# Chocolate_Vending_Machine_V2_2.net
KiCad netlist of a schematic drawn in Altium Designer
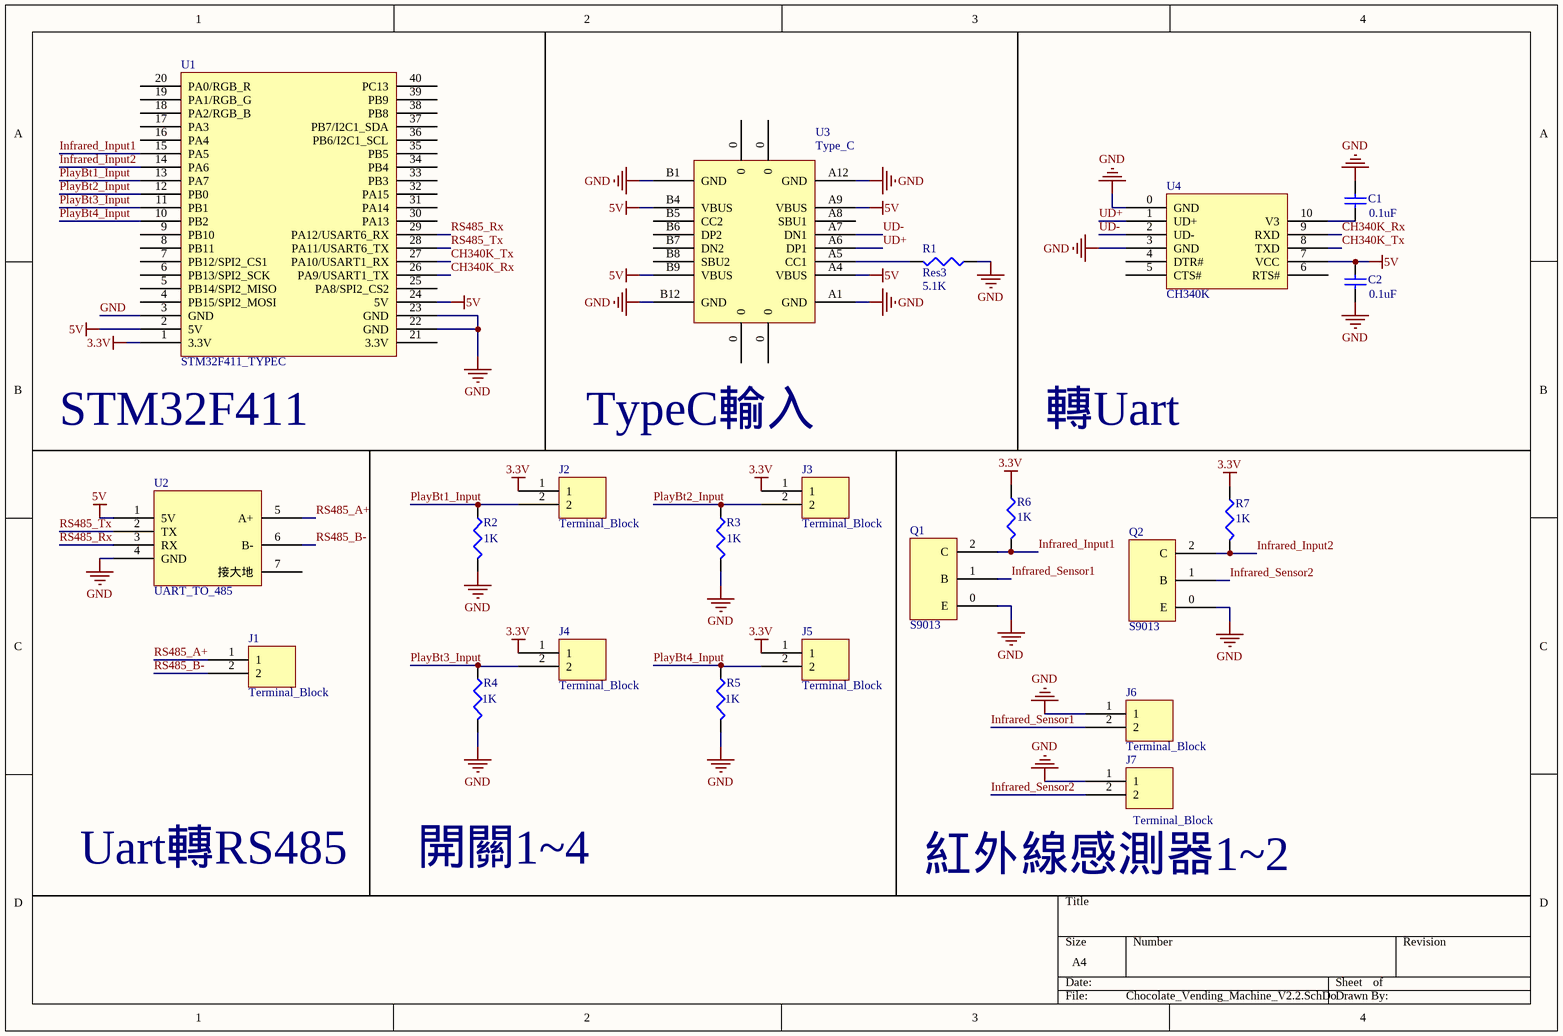
[diagram p0: Chocolate_Vending_Machine_V2.2.SchDoc]

(export (version "E")
  (design (tool "Eeschema 10.0.6"))
  (components
    (comp (ref "C1")
      (value "0.1uF")
      (footprint "1608[0603]")
      (description "Capacitor (Semiconductor SIM Model)")
      (fields (field (name "Comment") "Cap Semi") (field (name "PUBLISHER") "Altium Limited"))
      (libsource (lib "Miscellaneous Devices") (part "Cap Semi"))
    )
    (comp (ref "C2")
      (value "0.1uF")
      (footprint "1608[0603]")
      (description "Capacitor (Semiconductor SIM Model)")
      (fields (field (name "Comment") "Cap Semi") (field (name "PUBLISHER") "Altium Limited"))
      (libsource (lib "Miscellaneous Devices") (part "Cap Semi"))
    )
    (comp (ref "J1")
      (value "Terminal_Block")
      (footprint "terminal block")
      (libsource (lib "Lab_share") (part "Terminal Block"))
    )
    (comp (ref "J2")
      (value "Terminal_Block")
      (footprint "terminal block")
      (libsource (lib "Lab_share") (part "Terminal Block"))
    )
    (comp (ref "J3")
      (value "Terminal_Block")
      (footprint "terminal block")
      (libsource (lib "Lab_share") (part "Terminal Block"))
    )
    (comp (ref "J4")
      (value "Terminal_Block")
      (footprint "terminal block")
      (libsource (lib "Lab_share") (part "Terminal Block"))
    )
    (comp (ref "J5")
      (value "Terminal_Block")
      (footprint "terminal block")
      (libsource (lib "Lab_share") (part "Terminal Block"))
    )
    (comp (ref "J6")
      (value "Terminal_Block")
      (footprint "terminal block")
      (libsource (lib "Lab_share") (part "Terminal Block"))
    )
    (comp (ref "J7")
      (value "Terminal_Block")
      (footprint "terminal block")
      (libsource (lib "Lab_share") (part "Terminal Block"))
    )
    (comp (ref "Q1") (value "S9013") (footprint "S9013") (libsource (lib "Lab_share") (part "S9013")))
    (comp (ref "Q2") (value "S9013") (footprint "S9013") (libsource (lib "Lab_share") (part "S9013")))
    (comp (ref "R1")
      (value "Res3")
      (footprint "J1-0603")
      (description "Resistor")
      (fields (field (name "ALTIUM_VALUE") "5.1K") (field (name "PUBLISHER") "Altium Limited"))
      (libsource (lib "Miscellaneous Devices") (part "Res3"))
    )
    (comp (ref "R2")
      (value "1K")
      (footprint "J1-0603")
      (description "Resistor")
      (fields (field (name "Comment") "Res3") (field (name "PUBLISHER") "Altium Limited"))
      (libsource (lib "Miscellaneous Devices") (part "Res3"))
    )
    (comp (ref "R3")
      (value "1K")
      (footprint "J1-0603")
      (description "Resistor")
      (fields (field (name "Comment") "Res3") (field (name "PUBLISHER") "Altium Limited"))
      (libsource (lib "Miscellaneous Devices") (part "Res3"))
    )
    (comp (ref "R4")
      (value "1K")
      (footprint "J1-0603")
      (description "Resistor")
      (fields (field (name "Comment") "Res3") (field (name "PUBLISHER") "Altium Limited"))
      (libsource (lib "Miscellaneous Devices") (part "Res3"))
    )
    (comp (ref "R5")
      (value "1K")
      (footprint "J1-0603")
      (description "Resistor")
      (fields (field (name "Comment") "Res3") (field (name "PUBLISHER") "Altium Limited"))
      (libsource (lib "Miscellaneous Devices") (part "Res3"))
    )
    (comp (ref "R6")
      (value "1K")
      (footprint "J1-0603")
      (description "Resistor")
      (fields (field (name "Comment") "Res3") (field (name "PUBLISHER") "Altium Limited"))
      (libsource (lib "Miscellaneous Devices") (part "Res3"))
    )
    (comp (ref "R7")
      (value "1K")
      (footprint "J1-0603")
      (description "Resistor")
      (fields (field (name "Comment") "Res3") (field (name "PUBLISHER") "Altium Limited"))
      (libsource (lib "Miscellaneous Devices") (part "Res3"))
    )
    (comp (ref "U1")
      (value "STM32F411_TYPEC")
      (footprint "STM32F411_TypeC")
      (libsource (lib "Lab_share") (part "STM32F411_TYPEC"))
    )
    (comp (ref "U2")
      (value "UART_TO_485")
      (footprint "UART_TO_RS485")
      (libsource (lib "Lab_share") (part "UART_TO_485"))
    )
    (comp (ref "U3") (value "Type_C") (footprint "Type_C_V2") (libsource (lib "Lab_share") (part "Type_C")))
    (comp (ref "U4") (value "CH340K") (footprint "CH340K_V1") (libsource (lib "Lab_share") (part "CH340K")))
  )
  (nets
    (net (code "1") (name "/CH340K_Rx") (class "Default")
      (node (ref "U1") (pin "26") (pinfunction "PA9/USART1_TX_26") (pintype "passive"))
      (node (ref "U4") (pin "9") (pinfunction "RXD_9") (pintype "passive"))
    )
    (net (code "2") (name "/CH340K_Tx") (class "Default")
      (node (ref "U1") (pin "27") (pinfunction "PA10/USART1_RX_27") (pintype "passive"))
      (node (ref "U4") (pin "8") (pinfunction "TXD_8") (pintype "passive"))
    )
    (net (code "3") (name "/Infrared_Input1") (class "Default")
      (node (ref "Q1") (pin "2") (pinfunction "C_2") (pintype "passive"))
      (node (ref "R6") (pin "2") (pinfunction "2_2") (pintype "passive"))
      (node (ref "U1") (pin "15") (pinfunction "PA5_15") (pintype "passive"))
    )
    (net (code "4") (name "/Infrared_Input2") (class "Default")
      (node (ref "Q2") (pin "2") (pinfunction "C_2") (pintype "passive"))
      (node (ref "R7") (pin "2") (pinfunction "2_2") (pintype "passive"))
      (node (ref "U1") (pin "14") (pinfunction "PA6_14") (pintype "passive"))
    )
    (net (code "5") (name "/Infrared_Sensor1") (class "Default")
      (node (ref "J6") (pin "2") (pinfunction "2_2") (pintype "passive"))
      (node (ref "Q1") (pin "1") (pinfunction "B_1") (pintype "passive"))
    )
    (net (code "6") (name "/Infrared_Sensor2") (class "Default")
      (node (ref "J7") (pin "2") (pinfunction "2_2") (pintype "passive"))
      (node (ref "Q2") (pin "1") (pinfunction "B_1") (pintype "passive"))
    )
    (net (code "7") (name "/PlayBt1_Input") (class "Default")
      (node (ref "J2") (pin "2") (pinfunction "2_2") (pintype "passive"))
      (node (ref "R2") (pin "1") (pinfunction "1_1") (pintype "passive"))
      (node (ref "U1") (pin "13") (pinfunction "PA7_13") (pintype "passive"))
    )
    (net (code "8") (name "/PlayBt2_Input") (class "Default")
      (node (ref "J3") (pin "2") (pinfunction "2_2") (pintype "passive"))
      (node (ref "R3") (pin "1") (pinfunction "1_1") (pintype "passive"))
      (node (ref "U1") (pin "12") (pinfunction "PB0_12") (pintype "passive"))
    )
    (net (code "9") (name "/PlayBt3_Input") (class "Default")
      (node (ref "J4") (pin "2") (pinfunction "2_2") (pintype "passive"))
      (node (ref "R4") (pin "1") (pinfunction "1_1") (pintype "passive"))
      (node (ref "U1") (pin "11") (pinfunction "PB1_11") (pintype "passive"))
    )
    (net (code "10") (name "/PlayBt4_Input") (class "Default")
      (node (ref "J5") (pin "2") (pinfunction "2_2") (pintype "passive"))
      (node (ref "R5") (pin "1") (pinfunction "1_1") (pintype "passive"))
      (node (ref "U1") (pin "10") (pinfunction "PB2_10") (pintype "passive"))
    )
    (net (code "11") (name "/RS485_A+") (class "Default")
      (node (ref "J1") (pin "1") (pinfunction "1_1") (pintype "passive"))
      (node (ref "U2") (pin "5") (pinfunction "A+_5") (pintype "passive"))
    )
    (net (code "12") (name "/RS485_B-") (class "Default")
      (node (ref "J1") (pin "2") (pinfunction "2_2") (pintype "passive"))
      (node (ref "U2") (pin "6") (pinfunction "B-_6") (pintype "passive"))
    )
    (net (code "13") (name "/RS485_Rx") (class "Default")
      (node (ref "U1") (pin "29") (pinfunction "PA12/USART6_RX_29") (pintype "passive"))
      (node (ref "U2") (pin "3") (pinfunction "RX_3") (pintype "passive"))
    )
    (net (code "14") (name "/RS485_Tx") (class "Default")
      (node (ref "U1") (pin "28") (pinfunction "PA11/USART6_TX_28") (pintype "passive"))
      (node (ref "U2") (pin "2") (pinfunction "TX_2") (pintype "passive"))
    )
    (net (code "15") (name "/UD+") (class "Default")
      (node (ref "U3") (pin "A6") (pinfunction "DP1_A6") (pintype "passive"))
      (node (ref "U4") (pin "1") (pinfunction "UD+_1") (pintype "passive"))
    )
    (net (code "16") (name "/UD-") (class "Default")
      (node (ref "U3") (pin "A7") (pinfunction "DN1_A7") (pintype "passive"))
      (node (ref "U4") (pin "2") (pinfunction "UD-_2") (pintype "passive"))
    )
    (net (code "17") (name "3.3V") (class "Default")
      (node (ref "J2") (pin "1") (pinfunction "1_1") (pintype "passive"))
      (node (ref "J3") (pin "1") (pinfunction "1_1") (pintype "passive"))
      (node (ref "J4") (pin "1") (pinfunction "1_1") (pintype "passive"))
      (node (ref "J5") (pin "1") (pinfunction "1_1") (pintype "passive"))
      (node (ref "R6") (pin "1") (pinfunction "1_1") (pintype "passive"))
      (node (ref "R7") (pin "1") (pinfunction "1_1") (pintype "passive"))
      (node (ref "U1") (pin "1") (pinfunction "3.3V_1") (pintype "passive"))
    )
    (net (code "18") (name "5V") (class "Default")
      (node (ref "C2") (pin "2") (pinfunction "2_2") (pintype "passive"))
      (node (ref "U1") (pin "2") (pinfunction "5V_2") (pintype "passive"))
      (node (ref "U1") (pin "24") (pinfunction "5V_24") (pintype "passive"))
      (node (ref "U2") (pin "1") (pinfunction "5V_1") (pintype "passive"))
      (node (ref "U3") (pin "A4") (pinfunction "VBUS_A4") (pintype "passive"))
      (node (ref "U3") (pin "A9") (pinfunction "VBUS_A9") (pintype "passive"))
      (node (ref "U3") (pin "B4") (pinfunction "VBUS_B4") (pintype "passive"))
      (node (ref "U3") (pin "B9") (pinfunction "VBUS_B9") (pintype "passive"))
      (node (ref "U4") (pin "7") (pinfunction "VCC_7") (pintype "passive"))
    )
    (net (code "19") (name "GND") (class "Default")
      (node (ref "C1") (pin "2") (pinfunction "2_2") (pintype "passive"))
      (node (ref "C2") (pin "1") (pinfunction "1_1") (pintype "passive"))
      (node (ref "J6") (pin "1") (pinfunction "1_1") (pintype "passive"))
      (node (ref "J7") (pin "1") (pinfunction "1_1") (pintype "passive"))
      (node (ref "Q1") (pin "0") (pinfunction "E_0") (pintype "passive"))
      (node (ref "Q2") (pin "0") (pinfunction "E_0") (pintype "passive"))
      (node (ref "R1") (pin "1") (pinfunction "1_1") (pintype "passive"))
      (node (ref "R2") (pin "2") (pinfunction "2_2") (pintype "passive"))
      (node (ref "R3") (pin "2") (pinfunction "2_2") (pintype "passive"))
      (node (ref "R4") (pin "2") (pinfunction "2_2") (pintype "passive"))
      (node (ref "R5") (pin "2") (pinfunction "2_2") (pintype "passive"))
      (node (ref "U1") (pin "22") (pinfunction "GND_22") (pintype "passive"))
      (node (ref "U1") (pin "23") (pinfunction "GND_23") (pintype "passive"))
      (node (ref "U1") (pin "3") (pinfunction "GND_3") (pintype "passive"))
      (node (ref "U2") (pin "4") (pinfunction "GND_4") (pintype "passive"))
      (node (ref "U3") (pin "A1") (pinfunction "GND_A1") (pintype "passive"))
      (node (ref "U3") (pin "A12") (pinfunction "GND_A12") (pintype "passive"))
      (node (ref "U3") (pin "B1") (pinfunction "GND_B1") (pintype "passive"))
      (node (ref "U3") (pin "B12") (pinfunction "GND_B12") (pintype "passive"))
      (node (ref "U4") (pin "0") (pinfunction "GND_0") (pintype "passive"))
      (node (ref "U4") (pin "3") (pinfunction "GND_3") (pintype "passive"))
    )
    (net (code "20") (name "Net-(U3-CC1)") (class "Default")
      (node (ref "R1") (pin "2") (pinfunction "2_2") (pintype "passive"))
      (node (ref "U3") (pin "A5") (pinfunction "CC1_A5") (pintype "passive"))
    )
    (net (code "21") (name "Net-(U4-V3)") (class "Default")
      (node (ref "C1") (pin "1") (pinfunction "1_1") (pintype "passive"))
      (node (ref "U4") (pin "10") (pinfunction "V3_10") (pintype "passive"))
    )
    (net (code "22") (name "unconnected-(U1-3.3V-Pad21)") (class "Default")
      (node (ref "U1") (pin "21") (pinfunction "3.3V_21") (pintype "passive"))
    )
    (net (code "23") (name "unconnected-(U1-PA0{slash}RGB_R-Pad20)") (class "Default")
      (node (ref "U1") (pin "20") (pinfunction "PA0/RGB_R_20") (pintype "passive"))
    )
    (net (code "24") (name "unconnected-(U1-PA1{slash}RGB_G-Pad19)") (class "Default")
      (node (ref "U1") (pin "19") (pinfunction "PA1/RGB_G_19") (pintype "passive"))
    )
    (net (code "25") (name "unconnected-(U1-PA2{slash}RGB_B-Pad18)") (class "Default")
      (node (ref "U1") (pin "18") (pinfunction "PA2/RGB_B_18") (pintype "passive"))
    )
    (net (code "26") (name "unconnected-(U1-PA3-Pad17)") (class "Default")
      (node (ref "U1") (pin "17") (pinfunction "PA3_17") (pintype "passive"))
    )
    (net (code "27") (name "unconnected-(U1-PA4-Pad16)") (class "Default")
      (node (ref "U1") (pin "16") (pinfunction "PA4_16") (pintype "passive"))
    )
    (net (code "28") (name "unconnected-(U1-PA8{slash}SPI2_CS2-Pad25)") (class "Default")
      (node (ref "U1") (pin "25") (pinfunction "PA8/SPI2_CS2_25") (pintype "passive"))
    )
    (net (code "29") (name "unconnected-(U1-PA13-Pad30)") (class "Default")
      (node (ref "U1") (pin "30") (pinfunction "PA13_30") (pintype "passive"))
    )
    (net (code "30") (name "unconnected-(U1-PA14-Pad31)") (class "Default")
      (node (ref "U1") (pin "31") (pinfunction "PA14_31") (pintype "passive"))
    )
    (net (code "31") (name "unconnected-(U1-PA15-Pad32)") (class "Default")
      (node (ref "U1") (pin "32") (pinfunction "PA15_32") (pintype "passive"))
    )
    (net (code "32") (name "unconnected-(U1-PB3-Pad33)") (class "Default")
      (node (ref "U1") (pin "33") (pinfunction "PB3_33") (pintype "passive"))
    )
    (net (code "33") (name "unconnected-(U1-PB4-Pad34)") (class "Default")
      (node (ref "U1") (pin "34") (pinfunction "PB4_34") (pintype "passive"))
    )
    (net (code "34") (name "unconnected-(U1-PB5-Pad35)") (class "Default")
      (node (ref "U1") (pin "35") (pinfunction "PB5_35") (pintype "passive"))
    )
    (net (code "35") (name "unconnected-(U1-PB6{slash}I2C1_SCL-Pad36)") (class "Default")
      (node (ref "U1") (pin "36") (pinfunction "PB6/I2C1_SCL_36") (pintype "passive"))
    )
    (net (code "36") (name "unconnected-(U1-PB7{slash}I2C1_SDA-Pad37)") (class "Default")
      (node (ref "U1") (pin "37") (pinfunction "PB7/I2C1_SDA_37") (pintype "passive"))
    )
    (net (code "37") (name "unconnected-(U1-PB8-Pad38)") (class "Default")
      (node (ref "U1") (pin "38") (pinfunction "PB8_38") (pintype "passive"))
    )
    (net (code "38") (name "unconnected-(U1-PB9-Pad39)") (class "Default")
      (node (ref "U1") (pin "39") (pinfunction "PB9_39") (pintype "passive"))
    )
    (net (code "39") (name "unconnected-(U1-PB10-Pad9)") (class "Default")
      (node (ref "U1") (pin "9") (pinfunction "PB10_9") (pintype "passive"))
    )
    (net (code "40") (name "unconnected-(U1-PB11-Pad8)") (class "Default")
      (node (ref "U1") (pin "8") (pinfunction "PB11_8") (pintype "passive"))
    )
    (net (code "41") (name "unconnected-(U1-PB12{slash}SPI2_CS1-Pad7)") (class "Default")
      (node (ref "U1") (pin "7") (pinfunction "PB12/SPI2_CS1_7") (pintype "passive"))
    )
    (net (code "42") (name "unconnected-(U1-PB13{slash}SPI2_SCK-Pad6)") (class "Default")
      (node (ref "U1") (pin "6") (pinfunction "PB13/SPI2_SCK_6") (pintype "passive"))
    )
    (net (code "43") (name "unconnected-(U1-PB14{slash}SPI2_MISO-Pad5)") (class "Default")
      (node (ref "U1") (pin "5") (pinfunction "PB14/SPI2_MISO_5") (pintype "passive"))
    )
    (net (code "44") (name "unconnected-(U1-PB15{slash}SPI2_MOSI-Pad4)") (class "Default")
      (node (ref "U1") (pin "4") (pinfunction "PB15/SPI2_MOSI_4") (pintype "passive"))
    )
    (net (code "45") (name "unconnected-(U1-PC13-Pad40)") (class "Default")
      (node (ref "U1") (pin "40") (pinfunction "PC13_40") (pintype "passive"))
    )
    (net (code "46") (name "unconnected-(U2-接大地-Pad7)") (class "Default")
      (node (ref "U2") (pin "7") (pinfunction "接大地_7") (pintype "passive"))
    )
    (net (code "47") (name "unconnected-(U3-CC2-PadB5)") (class "Default")
      (node (ref "U3") (pin "B5") (pinfunction "CC2_B5") (pintype "passive"))
    )
    (net (code "48") (name "unconnected-(U3-DN2-PadB7)") (class "Default")
      (node (ref "U3") (pin "B7") (pinfunction "DN2_B7") (pintype "passive"))
    )
    (net (code "49") (name "unconnected-(U3-DP2-PadB6)") (class "Default")
      (node (ref "U3") (pin "B6") (pinfunction "DP2_B6") (pintype "passive"))
    )
    (net (code "50") (name "unconnected-(U3-Pad0)") (class "Default")
      (node (ref "U3") (pin "0") (pinfunction "0_0") (pintype "passive"))
    )
    (net (code "51") (name "unconnected-(U3-Pad0)_1") (class "Default")
      (node (ref "U3") (pin "0") (pinfunction "0_0") (pintype "passive"))
    )
    (net (code "52") (name "unconnected-(U3-Pad0)_2") (class "Default")
      (node (ref "U3") (pin "0") (pinfunction "0_0") (pintype "passive"))
    )
    (net (code "53") (name "unconnected-(U3-Pad0)_3") (class "Default")
      (node (ref "U3") (pin "0") (pinfunction "0_0") (pintype "passive"))
    )
    (net (code "54") (name "unconnected-(U3-SBU1-PadA8)") (class "Default")
      (node (ref "U3") (pin "A8") (pinfunction "SBU1_A8") (pintype "passive"))
    )
    (net (code "55") (name "unconnected-(U3-SBU2-PadB8)") (class "Default")
      (node (ref "U3") (pin "B8") (pinfunction "SBU2_B8") (pintype "passive"))
    )
    (net (code "56") (name "unconnected-(U4-CTS#-Pad5)") (class "Default")
      (node (ref "U4") (pin "5") (pinfunction "CTS#_5") (pintype "passive"))
    )
    (net (code "57") (name "unconnected-(U4-DTR#-Pad4)") (class "Default")
      (node (ref "U4") (pin "4") (pinfunction "DTR#_4") (pintype "passive"))
    )
    (net (code "58") (name "unconnected-(U4-RTS#-Pad6)") (class "Default")
      (node (ref "U4") (pin "6") (pinfunction "RTS#_6") (pintype "passive"))
    )
  )
)
